# Olimex_ESP32_Breakout_v1.net
KiCad netlist of a schematic drawn in EAGLE
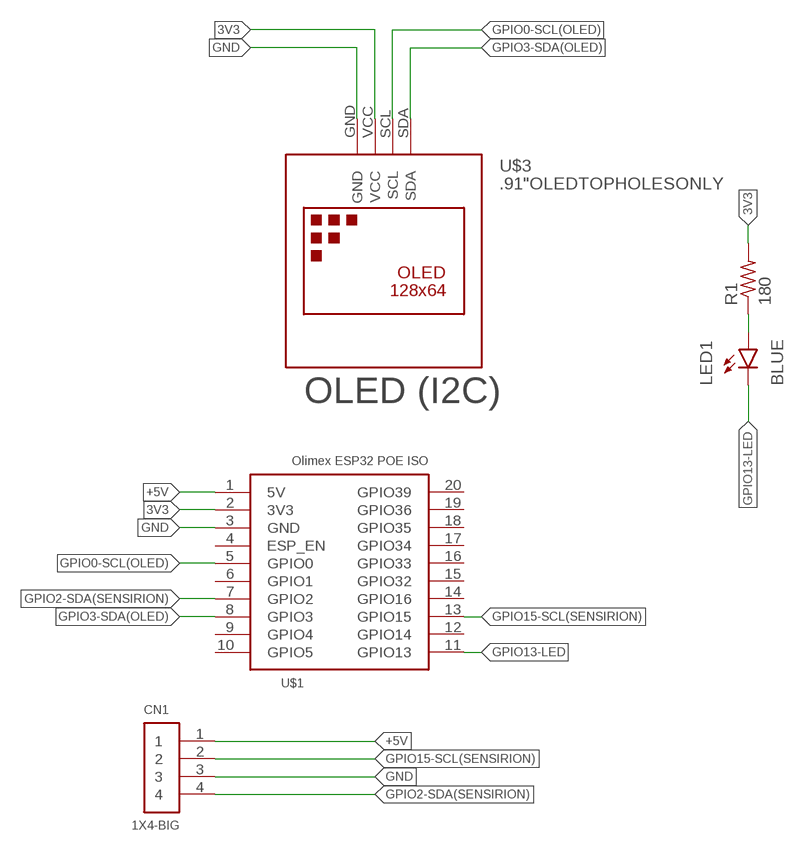
[diagram p0: schematic, sheet 1]

(export (version "E")
  (design (tool "Eeschema 10.0.6"))
  (components
    (comp (ref "CN1")
      (value "1X4-BIG")
      (footprint "eagle-import:1X04-BIG")
      (libsource (lib "eagle-import") (part "1X4-BIG"))
    )
    (comp (ref "LED1")
      (value "BLUE")
      (footprint "eagle-import:LED-1206")
      (libsource (lib "eagle-import") (part "LED-BLUE1206"))
    )
    (comp (ref "R1")
      (value "180")
      (footprint "eagle-import:R0805")
      (libsource (lib "eagle-import") (part "R-US_R0805"))
    )
    (comp (ref "U$1")
      (value "OLIMEX_POE_ISOPOEISO")
      (footprint "eagle-import:OLIMEX_POE_ISO")
      (libsource (lib "eagle-import") (part "OLIMEX_POE_ISOPOEISO"))
    )
    (comp (ref "U$3")
      (value ".91\"OLEDTOPHOLESONLY")
      (footprint "eagle-import:.96_OLED-TOPHOLESONLY")
      (libsource (lib "eagle-import") (part ".91{dblquote}OLEDTOPHOLESONLY"))
    )
  )
  (nets
    (net (code "1") (name "+5V") (class "Default")
      (node (ref "CN1") (pin "1") (pinfunction "1_1") (pintype "bidirectional"))
      (node (ref "U$1") (pin "1") (pinfunction "5V_1") (pintype "power_in"))
    )
    (net (code "2") (name "3V3") (class "Default")
      (node (ref "R1") (pin "2") (pinfunction "2_2") (pintype "passive"))
      (node (ref "U$1") (pin "2") (pinfunction "3V3_2") (pintype "power_in"))
      (node (ref "U$3") (pin "VCC") (pinfunction "VCC_VCC") (pintype "bidirectional"))
    )
    (net (code "3") (name "GND") (class "Default")
      (node (ref "CN1") (pin "3") (pinfunction "3_3") (pintype "bidirectional"))
      (node (ref "U$1") (pin "3") (pinfunction "GND_3") (pintype "power_in"))
      (node (ref "U$3") (pin "GND") (pinfunction "GND_GND") (pintype "bidirectional"))
    )
    (net (code "4") (name "GPIO0-SCL(OLED)") (class "Default")
      (node (ref "U$1") (pin "5") (pinfunction "GPIO0_5") (pintype "bidirectional"))
      (node (ref "U$3") (pin "SCL") (pinfunction "SCL_SCL") (pintype "bidirectional"))
    )
    (net (code "5") (name "GPIO2-SDA(SENSIRION)") (class "Default")
      (node (ref "CN1") (pin "4") (pinfunction "4_4") (pintype "bidirectional"))
      (node (ref "U$1") (pin "7") (pinfunction "GPIO2_7") (pintype "bidirectional"))
    )
    (net (code "6") (name "GPIO3-SDA(OLED)") (class "Default")
      (node (ref "U$1") (pin "8") (pinfunction "GPIO3_8") (pintype "bidirectional"))
      (node (ref "U$3") (pin "SDA") (pinfunction "SDA_SDA") (pintype "bidirectional"))
    )
    (net (code "7") (name "GPIO13-LED") (class "Default")
      (node (ref "LED1") (pin "C") (pinfunction "C_C") (pintype "passive"))
      (node (ref "U$1") (pin "11") (pinfunction "GPIO13_11") (pintype "bidirectional"))
    )
    (net (code "8") (name "GPIO15-SCL(SENSIRION)") (class "Default")
      (node (ref "CN1") (pin "2") (pinfunction "2_2") (pintype "bidirectional"))
      (node (ref "U$1") (pin "13") (pinfunction "GPIO15_13") (pintype "bidirectional"))
    )
    (net (code "9") (name "Net-(LED1-PadA)") (class "Default")
      (node (ref "LED1") (pin "A") (pinfunction "A_A") (pintype "passive"))
      (node (ref "R1") (pin "1") (pinfunction "1_1") (pintype "passive"))
    )
    (net (code "10") (name "unconnected-(U$1-ESP_EN-Pad4)") (class "Default")
      (node (ref "U$1") (pin "4") (pinfunction "ESP_EN_4") (pintype "bidirectional"))
    )
    (net (code "11") (name "unconnected-(U$1-GPIO1-Pad6)") (class "Default")
      (node (ref "U$1") (pin "6") (pinfunction "GPIO1_6") (pintype "bidirectional"))
    )
    (net (code "12") (name "unconnected-(U$1-GPIO4-Pad9)") (class "Default")
      (node (ref "U$1") (pin "9") (pinfunction "GPIO4_9") (pintype "bidirectional"))
    )
    (net (code "13") (name "unconnected-(U$1-GPIO5-Pad10)") (class "Default")
      (node (ref "U$1") (pin "10") (pinfunction "GPIO5_10") (pintype "bidirectional"))
    )
    (net (code "14") (name "unconnected-(U$1-GPIO14-Pad12)") (class "Default")
      (node (ref "U$1") (pin "12") (pinfunction "GPIO14_12") (pintype "bidirectional"))
    )
    (net (code "15") (name "unconnected-(U$1-GPIO16-Pad14)") (class "Default")
      (node (ref "U$1") (pin "14") (pinfunction "GPIO16_14") (pintype "bidirectional"))
    )
    (net (code "16") (name "unconnected-(U$1-GPIO32-Pad15)") (class "Default")
      (node (ref "U$1") (pin "15") (pinfunction "GPIO32_15") (pintype "bidirectional"))
    )
    (net (code "17") (name "unconnected-(U$1-GPIO33-Pad16)") (class "Default")
      (node (ref "U$1") (pin "16") (pinfunction "GPIO33_16") (pintype "bidirectional"))
    )
    (net (code "18") (name "unconnected-(U$1-GPIO34-Pad17)") (class "Default")
      (node (ref "U$1") (pin "17") (pinfunction "GPIO34_17") (pintype "input"))
    )
    (net (code "19") (name "unconnected-(U$1-GPIO35-Pad18)") (class "Default")
      (node (ref "U$1") (pin "18") (pinfunction "GPIO35_18") (pintype "input"))
    )
    (net (code "20") (name "unconnected-(U$1-GPIO36-Pad19)") (class "Default")
      (node (ref "U$1") (pin "19") (pinfunction "GPIO36_19") (pintype "input"))
    )
    (net (code "21") (name "unconnected-(U$1-GPIO39-Pad20)") (class "Default")
      (node (ref "U$1") (pin "20") (pinfunction "GPIO39_20") (pintype "input"))
    )
  )
)
